# Sens_SI7005.net
KiCad netlist of a schematic drawn in EAGLE
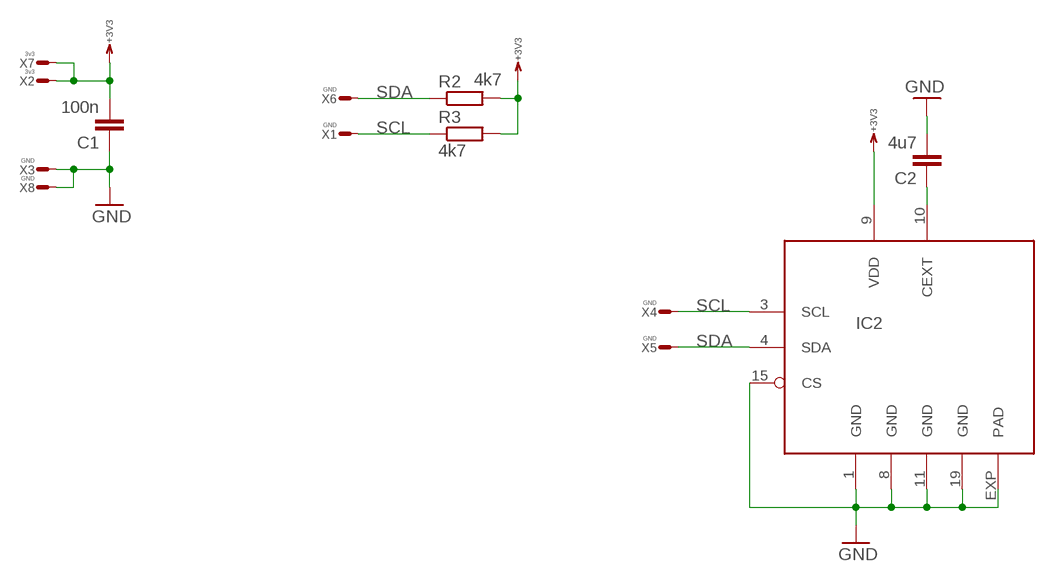
[diagram p0: schematic, sheet 1]

(export (version "E")
  (design (tool "Eeschema 10.0.6"))
  (components
    (comp (ref "C1")
      (value "100n")
      (footprint "eagle-import:0603")
      (libsource (lib "eagle-import") (part "C0603"))
    )
    (comp (ref "C2")
      (value "4u7")
      (footprint "eagle-import:0603")
      (libsource (lib "eagle-import") (part "C0603"))
    )
    (comp (ref "IC2")
      (value "SI7005")
      (footprint "eagle-import:QFN24")
      (libsource (lib "eagle-import") (part "SI7005"))
    )
    (comp (ref "R2")
      (value "4k7")
      (footprint "eagle-import:0603")
      (libsource (lib "eagle-import") (part "R0603"))
    )
    (comp (ref "R3")
      (value "4k7")
      (footprint "eagle-import:0603")
      (libsource (lib "eagle-import") (part "R0603"))
    )
    (comp (ref "X1")
      (value "GND")
      (footprint "eagle-import:T1.6_0.9")
      (libsource (lib "eagle-import") (part "WIREPADT1.6/0.9"))
    )
    (comp (ref "X2")
      (value "3v3")
      (footprint "eagle-import:T1.6_0.9")
      (libsource (lib "eagle-import") (part "WIREPADT1.6/0.9"))
    )
    (comp (ref "X3")
      (value "GND")
      (footprint "eagle-import:T1.6_0.9")
      (libsource (lib "eagle-import") (part "WIREPADT1.6/0.9"))
    )
    (comp (ref "X4")
      (value "GND")
      (footprint "eagle-import:T1.6_0.9")
      (libsource (lib "eagle-import") (part "WIREPADT1.6/0.9"))
    )
    (comp (ref "X5")
      (value "GND")
      (footprint "eagle-import:T1.6_0.9")
      (libsource (lib "eagle-import") (part "WIREPADT1.6/0.9"))
    )
    (comp (ref "X6")
      (value "GND")
      (footprint "eagle-import:T1.6_0.9")
      (libsource (lib "eagle-import") (part "WIREPADT1.6/0.9"))
    )
    (comp (ref "X7")
      (value "3v3")
      (footprint "eagle-import:T1.6_0.9")
      (libsource (lib "eagle-import") (part "WIREPADT1.6/0.9"))
    )
    (comp (ref "X8")
      (value "GND")
      (footprint "eagle-import:T1.6_0.9")
      (libsource (lib "eagle-import") (part "WIREPADT1.6/0.9"))
    )
  )
  (nets
    (net (code "1") (name "+3V3") (class "Default")
      (node (ref "C1") (pin "2") (pinfunction "2_2") (pintype "passive"))
      (node (ref "IC2") (pin "9") (pinfunction "VDD_9") (pintype "bidirectional"))
      (node (ref "R2") (pin "2") (pinfunction "2_2") (pintype "passive"))
      (node (ref "R3") (pin "2") (pinfunction "2_2") (pintype "passive"))
      (node (ref "X2") (pin "1") (pinfunction "S_1") (pintype "passive"))
      (node (ref "X7") (pin "1") (pinfunction "S_1") (pintype "passive"))
    )
    (net (code "2") (name "/SCL") (class "Default")
      (node (ref "IC2") (pin "3") (pinfunction "SCL_3") (pintype "bidirectional"))
      (node (ref "R3") (pin "1") (pinfunction "1_1") (pintype "passive"))
      (node (ref "X1") (pin "1") (pinfunction "S_1") (pintype "passive"))
      (node (ref "X4") (pin "1") (pinfunction "S_1") (pintype "passive"))
    )
    (net (code "3") (name "/SDA") (class "Default")
      (node (ref "IC2") (pin "4") (pinfunction "SDA_4") (pintype "bidirectional"))
      (node (ref "R2") (pin "1") (pinfunction "1_1") (pintype "passive"))
      (node (ref "X5") (pin "1") (pinfunction "S_1") (pintype "passive"))
      (node (ref "X6") (pin "1") (pinfunction "S_1") (pintype "passive"))
    )
    (net (code "4") (name "GND") (class "Default")
      (node (ref "C1") (pin "1") (pinfunction "1_1") (pintype "passive"))
      (node (ref "C2") (pin "2") (pinfunction "2_2") (pintype "passive"))
      (node (ref "IC2") (pin "1") (pinfunction "GND_1") (pintype "bidirectional"))
      (node (ref "IC2") (pin "11") (pinfunction "GND_11") (pintype "bidirectional"))
      (node (ref "IC2") (pin "15") (pinfunction "CS_15") (pintype "input"))
      (node (ref "IC2") (pin "19") (pinfunction "GND_19") (pintype "bidirectional"))
      (node (ref "IC2") (pin "8") (pinfunction "GND_8") (pintype "bidirectional"))
      (node (ref "IC2") (pin "EXP") (pinfunction "PAD_EXP") (pintype "bidirectional"))
      (node (ref "X3") (pin "1") (pinfunction "S_1") (pintype "passive"))
      (node (ref "X8") (pin "1") (pinfunction "S_1") (pintype "passive"))
    )
    (net (code "5") (name "Net-(IC2-CEXT)") (class "Default")
      (node (ref "C2") (pin "1") (pinfunction "1_1") (pintype "passive"))
      (node (ref "IC2") (pin "10") (pinfunction "CEXT_10") (pintype "bidirectional"))
    )
  )
)
